# pcc.net
KiCad netlist of a schematic drawn in EAGLE
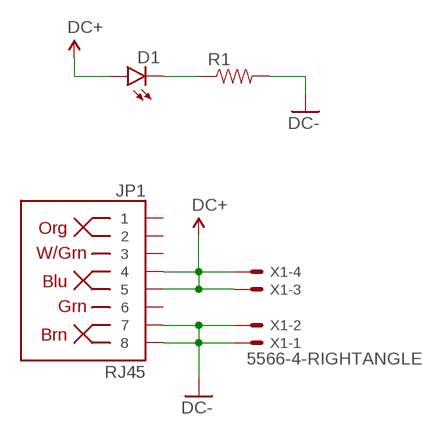
[diagram p0: schematic, sheet 1]

(export (version "E")
  (design (tool "Eeschema 10.0.6"))
  (components
    (comp (ref "D1")
      (value "LED0603")
      (footprint "eagle-import:LED-0603")
      (libsource (lib "eagle-import") (part "LED0603"))
    )
    (comp (ref "JP1")
      (value "RJ45")
      (footprint "eagle-import:RJ45-8")
      (libsource (lib "eagle-import") (part "RJ45-8PTH"))
    )
    (comp (ref "R1")
      (value "RESISTOR0603-RES")
      (footprint "eagle-import:0603-RES")
      (libsource (lib "eagle-import") (part "RESISTOR0603-RES"))
    )
    (comp (ref "X1")
      (value "5566-4-RIGHTANGLE")
      (footprint "eagle-import:5566-4")
      (libsource (lib "eagle-import") (part "5566-4-RIGHTANGLE"))
    )
  )
  (nets
    (net (code "1") (name "DC+") (class "Default")
      (node (ref "D1") (pin "A") (pinfunction "A_A") (pintype "passive"))
      (node (ref "JP1") (pin "4") (pinfunction "4_4") (pintype "bidirectional"))
      (node (ref "JP1") (pin "5") (pinfunction "5_5") (pintype "bidirectional"))
      (node (ref "X1") (pin "3") (pinfunction "S_3") (pintype "passive"))
      (node (ref "X1") (pin "4") (pinfunction "S_4") (pintype "passive"))
    )
    (net (code "2") (name "DC-") (class "Default")
      (node (ref "JP1") (pin "7") (pinfunction "7_7") (pintype "bidirectional"))
      (node (ref "JP1") (pin "8") (pinfunction "8_8") (pintype "bidirectional"))
      (node (ref "R1") (pin "2") (pinfunction "2_2") (pintype "passive"))
      (node (ref "X1") (pin "1") (pinfunction "S_1") (pintype "passive"))
      (node (ref "X1") (pin "2") (pinfunction "S_2") (pintype "passive"))
    )
    (net (code "3") (name "Net-(D1-PadC)") (class "Default")
      (node (ref "D1") (pin "C") (pinfunction "C_C") (pintype "passive"))
      (node (ref "R1") (pin "1") (pinfunction "1_1") (pintype "passive"))
    )
    (net (code "4") (name "unconnected-(JP1-Pad1)") (class "Default")
      (node (ref "JP1") (pin "1") (pinfunction "1_1") (pintype "bidirectional"))
    )
    (net (code "5") (name "unconnected-(JP1-Pad2)") (class "Default")
      (node (ref "JP1") (pin "2") (pinfunction "2_2") (pintype "bidirectional"))
    )
    (net (code "6") (name "unconnected-(JP1-Pad3)") (class "Default")
      (node (ref "JP1") (pin "3") (pinfunction "3_3") (pintype "bidirectional"))
    )
    (net (code "7") (name "unconnected-(JP1-Pad6)") (class "Default")
      (node (ref "JP1") (pin "6") (pinfunction "6_6") (pintype "bidirectional"))
    )
  )
)
